# Shield.net
KiCad netlist of a schematic drawn in EAGLE
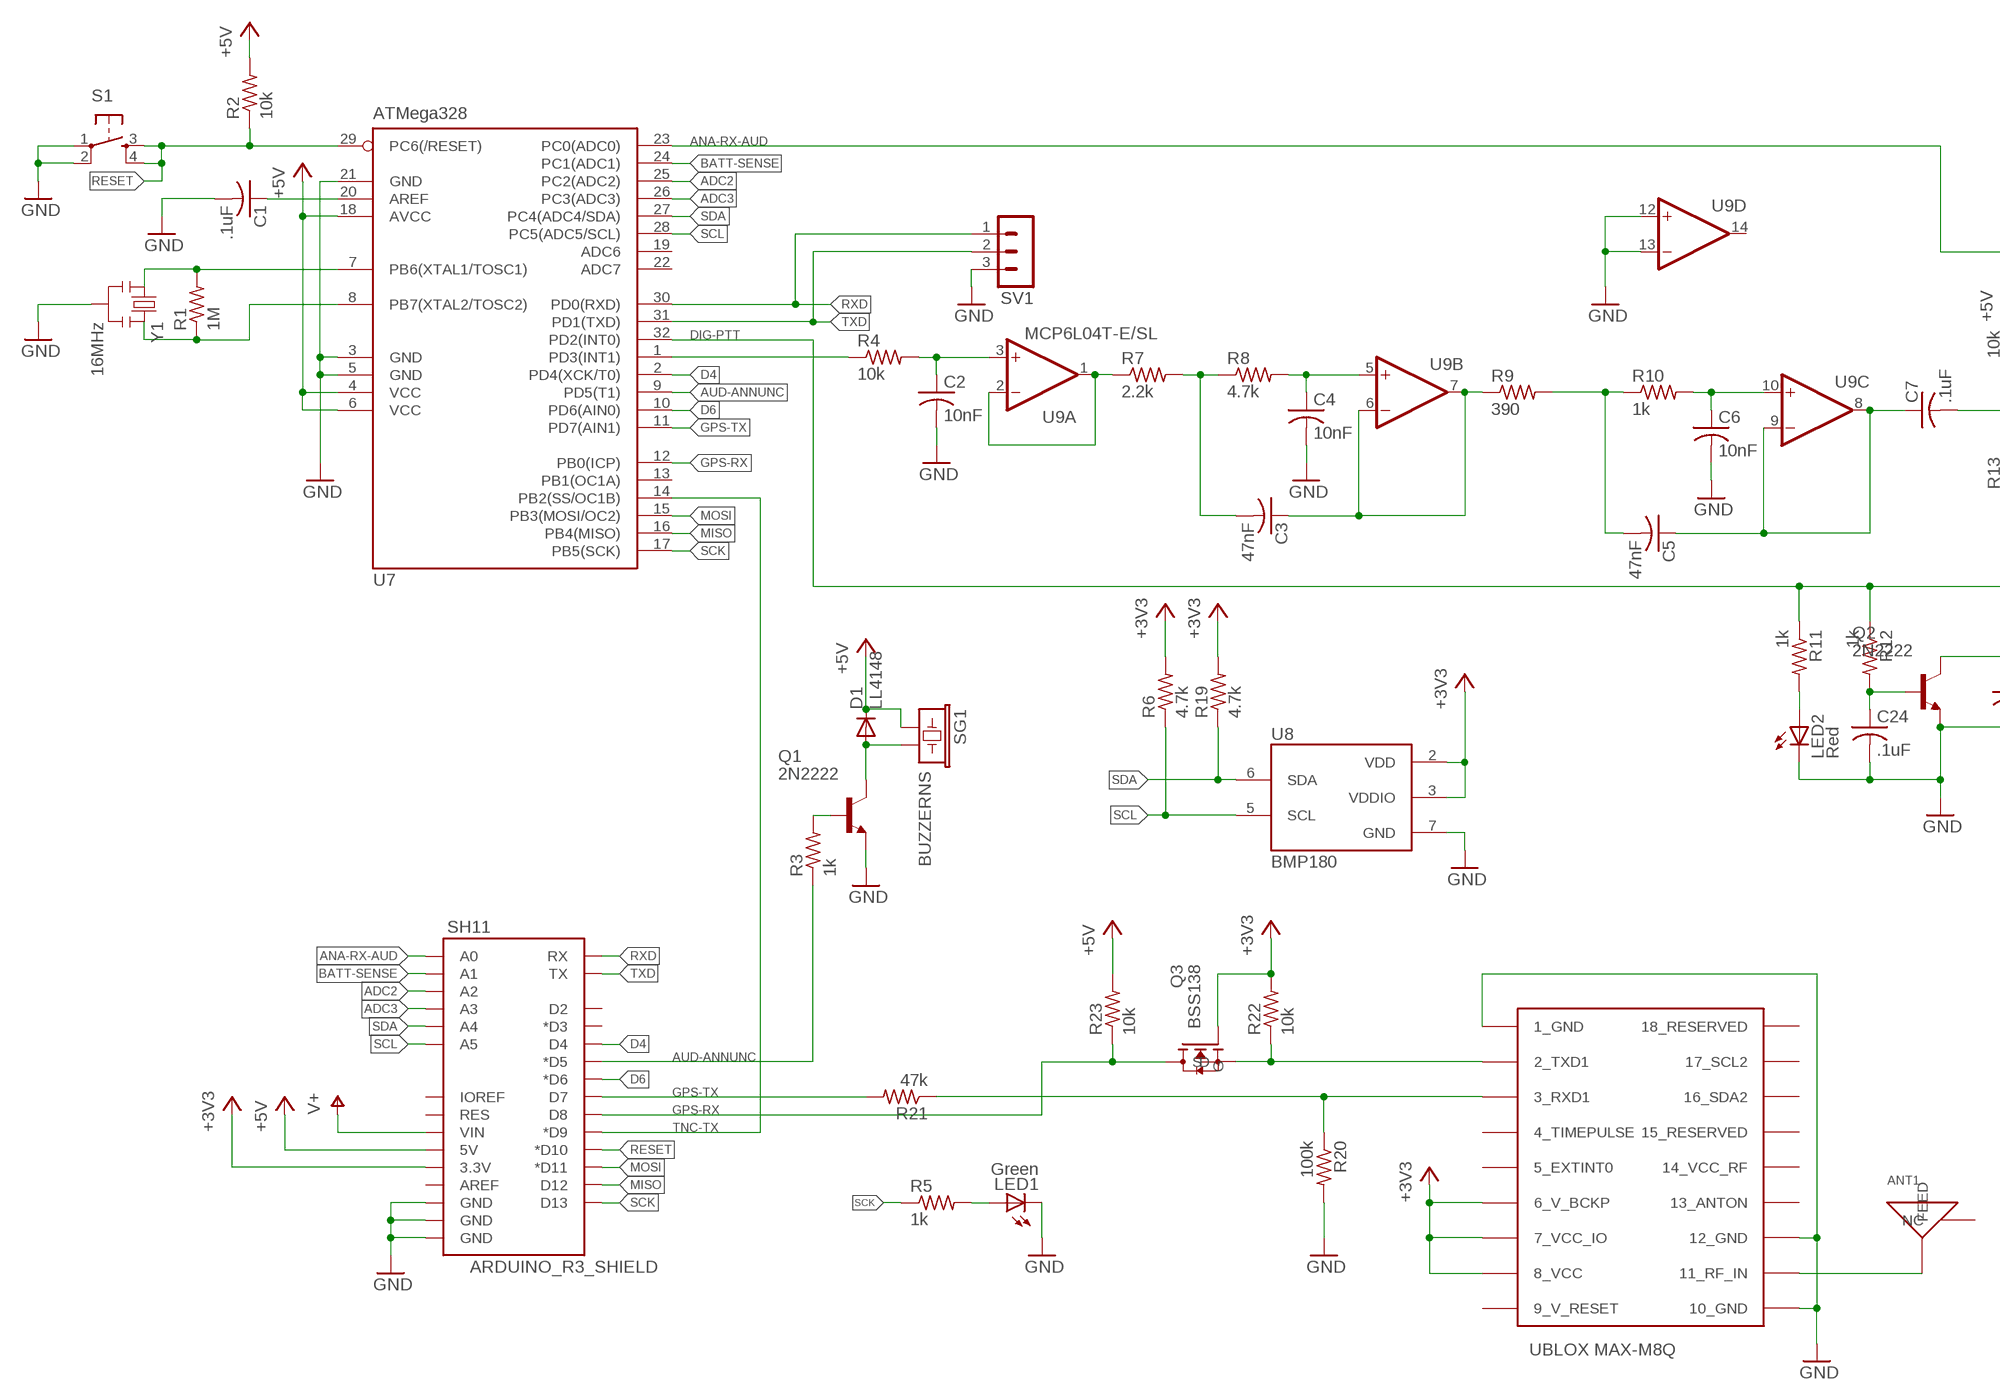
[diagram p0: schematic, sheet 1, part 1 of 2]
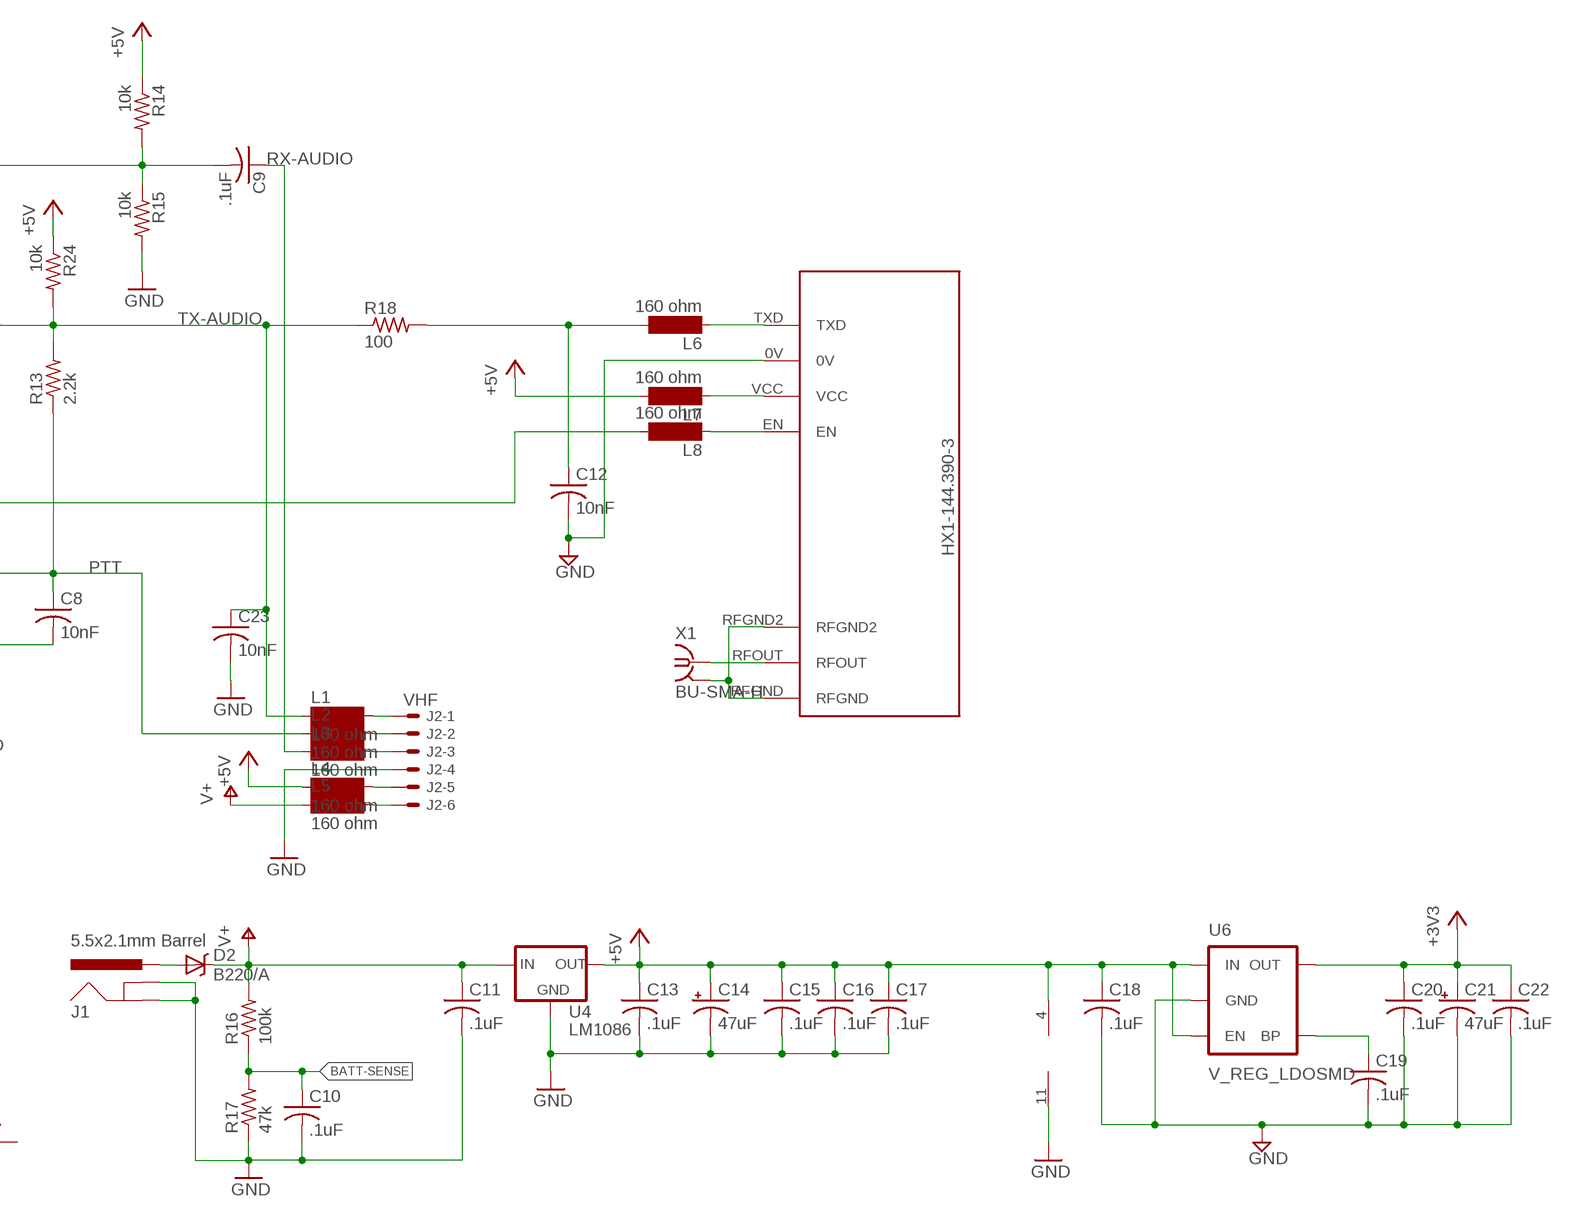
[diagram p1: schematic, sheet 1, part 2 of 2]

(export (version "E")
  (design (tool "Eeschema 10.0.6"))
  (components
    (comp (ref "ANT1")
      (value "GPS_ANT_SMDBAR")
      (footprint "eagle-import:1575AT43A40")
      (libsource (lib "eagle-import") (part "GPS_ANT_SMDBAR"))
    )
    (comp (ref "C1")
      (value ".1uF")
      (footprint "eagle-import:C0805")
      (libsource (lib "eagle-import") (part "C-USC0805"))
    )
    (comp (ref "C2")
      (value "10nF")
      (footprint "eagle-import:C0805")
      (libsource (lib "eagle-import") (part "C-USC0805"))
    )
    (comp (ref "C3")
      (value "47nF")
      (footprint "eagle-import:C0805")
      (libsource (lib "eagle-import") (part "C-USC0805"))
    )
    (comp (ref "C4")
      (value "10nF")
      (footprint "eagle-import:C0805")
      (libsource (lib "eagle-import") (part "C-USC0805"))
    )
    (comp (ref "C5")
      (value "47nF")
      (footprint "eagle-import:C0805")
      (libsource (lib "eagle-import") (part "C-USC0805"))
    )
    (comp (ref "C6")
      (value "10nF")
      (footprint "eagle-import:C0805")
      (libsource (lib "eagle-import") (part "C-USC0805"))
    )
    (comp (ref "C7")
      (value ".1uF")
      (footprint "eagle-import:C0805")
      (libsource (lib "eagle-import") (part "C-USC0805"))
    )
    (comp (ref "C8")
      (value "10nF")
      (footprint "eagle-import:C0805")
      (libsource (lib "eagle-import") (part "C-USC0805"))
    )
    (comp (ref "C9")
      (value ".1uF")
      (footprint "eagle-import:C0805")
      (libsource (lib "eagle-import") (part "C-USC0805"))
    )
    (comp (ref "C10")
      (value ".1uF")
      (footprint "eagle-import:C0805")
      (libsource (lib "eagle-import") (part "C-USC0805"))
    )
    (comp (ref "C11")
      (value ".1uF")
      (footprint "eagle-import:C0805")
      (libsource (lib "eagle-import") (part "C-USC0805"))
    )
    (comp (ref "C12")
      (value "10nF")
      (footprint "eagle-import:C0805")
      (libsource (lib "eagle-import") (part "C-USC0805"))
    )
    (comp (ref "C13")
      (value ".1uF")
      (footprint "eagle-import:C0805")
      (libsource (lib "eagle-import") (part "C-USC0805"))
    )
    (comp (ref "C14")
      (value "47uF")
      (footprint "eagle-import:153CLV-0605")
      (libsource (lib "eagle-import") (part "CPOL-US153CLV-0605"))
    )
    (comp (ref "C15")
      (value ".1uF")
      (footprint "eagle-import:C0805")
      (libsource (lib "eagle-import") (part "C-USC0805"))
    )
    (comp (ref "C16")
      (value ".1uF")
      (footprint "eagle-import:C0805")
      (libsource (lib "eagle-import") (part "C-USC0805"))
    )
    (comp (ref "C17")
      (value ".1uF")
      (footprint "eagle-import:C0805")
      (libsource (lib "eagle-import") (part "C-USC0805"))
    )
    (comp (ref "C18")
      (value ".1uF")
      (footprint "eagle-import:C0805")
      (libsource (lib "eagle-import") (part "C-USC0805"))
    )
    (comp (ref "C19")
      (value ".1uF")
      (footprint "eagle-import:C0805")
      (libsource (lib "eagle-import") (part "C-USC0805"))
    )
    (comp (ref "C20")
      (value ".1uF")
      (footprint "eagle-import:C0805")
      (libsource (lib "eagle-import") (part "C-USC0805"))
    )
    (comp (ref "C21")
      (value "47uF")
      (footprint "eagle-import:153CLV-0605")
      (libsource (lib "eagle-import") (part "CPOL-US153CLV-0605"))
    )
    (comp (ref "C22")
      (value ".1uF")
      (footprint "eagle-import:C0805")
      (libsource (lib "eagle-import") (part "C-USC0805"))
    )
    (comp (ref "C23")
      (value "10nF")
      (footprint "eagle-import:C0805")
      (libsource (lib "eagle-import") (part "C-USC0805"))
    )
    (comp (ref "C24")
      (value ".1uF")
      (footprint "eagle-import:C0805")
      (libsource (lib "eagle-import") (part "C-USC0805"))
    )
    (comp (ref "D1")
      (value "LL4148")
      (footprint "eagle-import:MINIMELF")
      (libsource (lib "eagle-import") (part "DIODE-MINIMELF"))
    )
    (comp (ref "D2")
      (value "B220/A")
      (footprint "eagle-import:SMA-DIODE")
      (libsource (lib "eagle-import") (part "B340A"))
    )
    (comp (ref "J1")
      (value "5.5x2.1mm Barrel")
      (footprint "eagle-import:POWER_JACK_SMD")
      (libsource (lib "eagle-import") (part "POWER_JACKSMD"))
    )
    (comp (ref "J2")
      (value "VHF")
      (footprint "eagle-import:7395-06")
      (fields (field (name "DIGIKEY") "WM4304-ND"))
      (libsource (lib "eagle-import") (part "22-?-0605-7068"))
    )
    (comp (ref "L1")
      (value "160 ohm")
      (footprint "eagle-import:SM-1206")
      (libsource (lib "eagle-import") (part "SM-1206"))
    )
    (comp (ref "L2")
      (value "160 ohm")
      (footprint "eagle-import:SM-1206")
      (libsource (lib "eagle-import") (part "SM-1206"))
    )
    (comp (ref "L3")
      (value "160 ohm")
      (footprint "eagle-import:SM-1206")
      (libsource (lib "eagle-import") (part "SM-1206"))
    )
    (comp (ref "L4")
      (value "160 ohm")
      (footprint "eagle-import:SM-1206")
      (libsource (lib "eagle-import") (part "SM-1206"))
    )
    (comp (ref "L5")
      (value "160 ohm")
      (footprint "eagle-import:SM-1206")
      (libsource (lib "eagle-import") (part "SM-1206"))
    )
    (comp (ref "L6")
      (value "160 ohm")
      (footprint "eagle-import:SM-1206")
      (libsource (lib "eagle-import") (part "SM-1206"))
    )
    (comp (ref "L7")
      (value "160 ohm")
      (footprint "eagle-import:SM-1206")
      (libsource (lib "eagle-import") (part "SM-1206"))
    )
    (comp (ref "L8")
      (value "160 ohm")
      (footprint "eagle-import:SM-1206")
      (libsource (lib "eagle-import") (part "SM-1206"))
    )
    (comp (ref "LED1")
      (value "Green")
      (footprint "eagle-import:CHIPLED_1206")
      (libsource (lib "eagle-import") (part "LEDCHIPLED_1206"))
    )
    (comp (ref "LED2")
      (value "Red")
      (footprint "eagle-import:CHIPLED_1206")
      (libsource (lib "eagle-import") (part "LEDCHIPLED_1206"))
    )
    (comp (ref "Q1")
      (value "2N2222")
      (footprint "eagle-import:SOT23-BEC")
      (libsource (lib "eagle-import") (part "BC817SMD-16LT1"))
    )
    (comp (ref "Q2")
      (value "2N2222")
      (footprint "eagle-import:SOT23-BEC")
      (libsource (lib "eagle-import") (part "BC817SMD-16LT1"))
    )
    (comp (ref "Q3")
      (value "BSS138")
      (footprint "eagle-import:BSS138")
      (libsource (lib "eagle-import") (part "BSS138"))
    )
    (comp (ref "R1")
      (value "1M")
      (footprint "eagle-import:R0805")
      (libsource (lib "eagle-import") (part "R-US_R0805"))
    )
    (comp (ref "R2")
      (value "10k")
      (footprint "eagle-import:R0805")
      (libsource (lib "eagle-import") (part "R-US_R0805"))
    )
    (comp (ref "R3")
      (value "1k")
      (footprint "eagle-import:R0805")
      (libsource (lib "eagle-import") (part "R-US_R0805"))
    )
    (comp (ref "R4")
      (value "10k")
      (footprint "eagle-import:R0805")
      (libsource (lib "eagle-import") (part "R-US_R0805"))
    )
    (comp (ref "R5")
      (value "1k")
      (footprint "eagle-import:R0805")
      (libsource (lib "eagle-import") (part "R-US_R0805"))
    )
    (comp (ref "R6")
      (value "4.7k")
      (footprint "eagle-import:R0805")
      (libsource (lib "eagle-import") (part "R-US_R0805"))
    )
    (comp (ref "R7")
      (value "2.2k")
      (footprint "eagle-import:R0805")
      (libsource (lib "eagle-import") (part "R-US_R0805"))
    )
    (comp (ref "R8")
      (value "4.7k")
      (footprint "eagle-import:R0805")
      (libsource (lib "eagle-import") (part "R-US_R0805"))
    )
    (comp (ref "R9")
      (value "390")
      (footprint "eagle-import:R0805")
      (libsource (lib "eagle-import") (part "R-US_R0805"))
    )
    (comp (ref "R10")
      (value "1k")
      (footprint "eagle-import:R0805")
      (libsource (lib "eagle-import") (part "R-US_R0805"))
    )
    (comp (ref "R11")
      (value "1k")
      (footprint "eagle-import:R0805")
      (libsource (lib "eagle-import") (part "R-US_R0805"))
    )
    (comp (ref "R12")
      (value "1k")
      (footprint "eagle-import:R0805")
      (libsource (lib "eagle-import") (part "R-US_R0805"))
    )
    (comp (ref "R13")
      (value "2.2k")
      (footprint "eagle-import:R0805")
      (libsource (lib "eagle-import") (part "R-US_R0805"))
    )
    (comp (ref "R14")
      (value "10k")
      (footprint "eagle-import:R0805")
      (libsource (lib "eagle-import") (part "R-US_R0805"))
    )
    (comp (ref "R15")
      (value "10k")
      (footprint "eagle-import:R0805")
      (libsource (lib "eagle-import") (part "R-US_R0805"))
    )
    (comp (ref "R16")
      (value "100k")
      (footprint "eagle-import:R0805")
      (libsource (lib "eagle-import") (part "R-US_R0805"))
    )
    (comp (ref "R17")
      (value "47k")
      (footprint "eagle-import:R0805")
      (libsource (lib "eagle-import") (part "R-US_R0805"))
    )
    (comp (ref "R18")
      (value "100")
      (footprint "eagle-import:R0805")
      (libsource (lib "eagle-import") (part "R-US_R0805"))
    )
    (comp (ref "R19")
      (value "4.7k")
      (footprint "eagle-import:R0805")
      (libsource (lib "eagle-import") (part "R-US_R0805"))
    )
    (comp (ref "R20")
      (value "100k")
      (footprint "eagle-import:R0805")
      (libsource (lib "eagle-import") (part "R-US_R0805"))
    )
    (comp (ref "R21")
      (value "47k")
      (footprint "eagle-import:R0805")
      (libsource (lib "eagle-import") (part "R-US_R0805"))
    )
    (comp (ref "R22")
      (value "10k")
      (footprint "eagle-import:R0805")
      (libsource (lib "eagle-import") (part "R-US_R0805"))
    )
    (comp (ref "R23")
      (value "10k")
      (footprint "eagle-import:R0805")
      (libsource (lib "eagle-import") (part "R-US_R0805"))
    )
    (comp (ref "R24")
      (value "10k")
      (footprint "eagle-import:R0805")
      (libsource (lib "eagle-import") (part "R-US_R0805"))
    )
    (comp (ref "S1")
      (value "TAC_SWITCHSMD")
      (footprint "eagle-import:TACTILE_SWITCH_SMD")
      (libsource (lib "eagle-import") (part "TAC_SWITCHSMD"))
    )
    (comp (ref "SG1")
      (value "BUZZERNS")
      (footprint "eagle-import:BUZZER-12MM-NS")
      (libsource (lib "eagle-import") (part "BUZZERNS"))
    )
    (comp (ref "SH11")
      (value "ARDUINO_R3_SHIELD")
      (footprint "eagle-import:UNO_R3_SHIELD")
      (libsource (lib "eagle-import") (part "ARDUINO_R3_SHIELD"))
    )
    (comp (ref "SV1")
      (value "MA03-1")
      (footprint "eagle-import:MA03-1")
      (libsource (lib "eagle-import") (part "MA03-1"))
    )
    (comp (ref "U3")
      (value "UBLOX_MAX")
      (footprint "eagle-import:UBLOX_MAX")
      (fields (field (name "ALT-PART") "UBLOX MAX-M8Q"))
      (libsource (lib "eagle-import") (part "UBLOX_MAX"))
    )
    (comp (ref "U4")
      (value "LM1086")
      (footprint "eagle-import:TO263")
      (libsource (lib "eagle-import") (part "LM1086TO263"))
    )
    (comp (ref "U5")
      (value "RADIOMETRIX-HX1")
      (footprint "eagle-import:RADIOMETRIX-HX1")
      (fields (field (name "ALT-PART") "HX1-144.390-3"))
      (libsource (lib "eagle-import") (part "RADIOMETRIX-HX1"))
    )
    (comp (ref "U6")
      (value "V_REG_LDOSMD")
      (footprint "eagle-import:SOT23-5")
      (libsource (lib "eagle-import") (part "V_REG_LDOSMD"))
    )
    (comp (ref "U7")
      (value "ATMega328")
      (footprint "eagle-import:TQFP32-08")
      (fields (field (name "MPN") "ATMEGA8-16AU"))
      (libsource (lib "eagle-import") (part "MEGA8-AI"))
    )
    (comp (ref "U8")
      (value "BMP180")
      (footprint "eagle-import:BMP180")
      (libsource (lib "eagle-import") (part "BMP180"))
    )
    (comp (ref "U9")
      (value "LMV324M")
      (footprint "eagle-import:SO14")
      (fields (field (name "ALT-PART") "MCP6L04T-E/SL") (field (name "DIGIKEY") "MCP6L04T-E/SLCT-ND"))
      (libsource (lib "eagle-import") (part "LMV324?M"))
    )
    (comp (ref "X1")
      (value "BU-SMA-H")
      (footprint "eagle-import:BU-SMA-H")
      (libsource (lib "eagle-import") (part "BU-SMA-H"))
    )
    (comp (ref "Y1")
      (value "16MHz")
      (footprint "eagle-import:RESONATOR-SMD")
      (libsource (lib "eagle-import") (part "RESONATOR16MHZ"))
    )
  )
  (nets
    (net (code "1") (name "+3V3") (class "Default")
      (node (ref "C20") (pin "1") (pinfunction "1_1") (pintype "passive"))
      (node (ref "C21") (pin "+") (pinfunction "+_+") (pintype "passive"))
      (node (ref "C22") (pin "1") (pinfunction "1_1") (pintype "passive"))
      (node (ref "Q3") (pin "G") (pinfunction "G_G") (pintype "passive"))
      (node (ref "R19") (pin "2") (pinfunction "2_2") (pintype "passive"))
      (node (ref "R22") (pin "2") (pinfunction "2_2") (pintype "passive"))
      (node (ref "R6") (pin "2") (pinfunction "2_2") (pintype "passive"))
      (node (ref "SH11") (pin "3.3V") (pinfunction "3.3V_3.3V") (pintype "bidirectional"))
      (node (ref "U3") (pin "6_V_BCKP") (pinfunction "6_V_BCKP_6_V_BCKP") (pintype "bidirectional"))
      (node (ref "U3") (pin "7_VCC_IO") (pinfunction "7_VCC_IO_7_VCC_IO") (pintype "power_in"))
      (node (ref "U3") (pin "8_VCC") (pinfunction "8_VCC_8_VCC") (pintype "power_in"))
      (node (ref "U6") (pin "5") (pinfunction "OUT_5") (pintype "passive"))
      (node (ref "U8") (pin "2") (pinfunction "VDD_2") (pintype "power_in"))
      (node (ref "U8") (pin "3") (pinfunction "VDDIO_3") (pintype "power_in"))
    )
    (net (code "2") (name "+5V") (class "Default")
      (node (ref "C13") (pin "1") (pinfunction "1_1") (pintype "passive"))
      (node (ref "C14") (pin "+") (pinfunction "+_+") (pintype "passive"))
      (node (ref "C15") (pin "1") (pinfunction "1_1") (pintype "passive"))
      (node (ref "C16") (pin "1") (pinfunction "1_1") (pintype "passive"))
      (node (ref "C17") (pin "1") (pinfunction "1_1") (pintype "passive"))
      (node (ref "C18") (pin "1") (pinfunction "1_1") (pintype "passive"))
      (node (ref "D1") (pin "C") (pinfunction "C_C") (pintype "passive"))
      (node (ref "L4") (pin "1") (pinfunction "1_1") (pintype "passive"))
      (node (ref "L7") (pin "2") (pinfunction "2_2") (pintype "passive"))
      (node (ref "R14") (pin "1") (pinfunction "1_1") (pintype "passive"))
      (node (ref "R2") (pin "2") (pinfunction "2_2") (pintype "passive"))
      (node (ref "R23") (pin "2") (pinfunction "2_2") (pintype "passive"))
      (node (ref "R24") (pin "1") (pinfunction "1_1") (pintype "passive"))
      (node (ref "SG1") (pin "+") (pinfunction "1_+") (pintype "passive"))
      (node (ref "SH11") (pin "5V") (pinfunction "5V_5V") (pintype "bidirectional"))
      (node (ref "U4") (pin "2") (pinfunction "OUT_2") (pintype "passive"))
      (node (ref "U6") (pin "1") (pinfunction "IN_1") (pintype "input"))
      (node (ref "U6") (pin "3") (pinfunction "EN_3") (pintype "input"))
      (node (ref "U7") (pin "18") (pinfunction "AVCC_18") (pintype "power_in"))
      (node (ref "U7") (pin "4") (pinfunction "VCC_4") (pintype "power_in"))
      (node (ref "U7") (pin "6") (pinfunction "VCC_6") (pintype "power_in"))
      (node (ref "U9") (pin "4") (pinfunction "V+_4") (pintype "power_in"))
    )
    (net (code "3") (name "/9_V_RESET") (class "Default")
      (node (ref "U3") (pin "9_V_RESET") (pinfunction "9_V_RESET_9_V_RESET") (pintype "power_in"))
    )
    (net (code "4") (name "/DIG-PTT") (class "Default")
      (node (ref "L8") (pin "2") (pinfunction "2_2") (pintype "passive"))
      (node (ref "R11") (pin "1") (pinfunction "1_1") (pintype "passive"))
      (node (ref "R12") (pin "1") (pinfunction "1_1") (pintype "passive"))
      (node (ref "U7") (pin "32") (pinfunction "PD2(INT0)_32") (pintype "bidirectional"))
    )
    (net (code "5") (name "/PTT") (class "Default")
      (node (ref "C8") (pin "1") (pinfunction "1_1") (pintype "passive"))
      (node (ref "L2") (pin "1") (pinfunction "1_1") (pintype "passive"))
      (node (ref "Q2") (pin "C") (pinfunction "C_C") (pintype "passive"))
      (node (ref "R13") (pin "1") (pinfunction "1_1") (pintype "passive"))
    )
    (net (code "6") (name "/RX-AUDIO") (class "Default")
      (node (ref "C9") (pin "1") (pinfunction "1_1") (pintype "passive"))
      (node (ref "L3") (pin "1") (pinfunction "1_1") (pintype "passive"))
    )
    (net (code "7") (name "/TNC-TX") (class "Default")
      (node (ref "SH11") (pin "D9") (pinfunction "*D9_D9") (pintype "bidirectional"))
      (node (ref "U7") (pin "14") (pinfunction "PB2(SS/OC1B)_14") (pintype "bidirectional"))
    )
    (net (code "8") (name "/TX-AUDIO") (class "Default")
      (node (ref "C23") (pin "1") (pinfunction "1_1") (pintype "passive"))
      (node (ref "C7") (pin "2") (pinfunction "2_2") (pintype "passive"))
      (node (ref "L1") (pin "1") (pinfunction "1_1") (pintype "passive"))
      (node (ref "R13") (pin "2") (pinfunction "2_2") (pintype "passive"))
      (node (ref "R18") (pin "1") (pinfunction "1_1") (pintype "passive"))
      (node (ref "R24") (pin "2") (pinfunction "2_2") (pintype "passive"))
    )
    (net (code "9") (name "ADC2") (class "Default")
      (node (ref "SH11") (pin "A2") (pinfunction "A2_A2") (pintype "bidirectional"))
      (node (ref "U7") (pin "25") (pinfunction "PC2(ADC2)_25") (pintype "bidirectional"))
    )
    (net (code "10") (name "ADC3") (class "Default")
      (node (ref "SH11") (pin "A3") (pinfunction "A3_A3") (pintype "bidirectional"))
      (node (ref "U7") (pin "26") (pinfunction "PC3(ADC3)_26") (pintype "bidirectional"))
    )
    (net (code "11") (name "ANA-RX-AUD") (class "Default")
      (node (ref "C9") (pin "2") (pinfunction "2_2") (pintype "passive"))
      (node (ref "R14") (pin "2") (pinfunction "2_2") (pintype "passive"))
      (node (ref "R15") (pin "1") (pinfunction "1_1") (pintype "passive"))
      (node (ref "SH11") (pin "A0") (pinfunction "A0_A0") (pintype "bidirectional"))
      (node (ref "U7") (pin "23") (pinfunction "PC0(ADC0)_23") (pintype "bidirectional"))
    )
    (net (code "12") (name "AUD-ANNUNC") (class "Default")
      (node (ref "R3") (pin "1") (pinfunction "1_1") (pintype "passive"))
      (node (ref "SH11") (pin "D5") (pinfunction "*D5_D5") (pintype "bidirectional"))
      (node (ref "U7") (pin "9") (pinfunction "PD5(T1)_9") (pintype "bidirectional"))
    )
    (net (code "13") (name "BATT-SENSE") (class "Default")
      (node (ref "C10") (pin "1") (pinfunction "1_1") (pintype "passive"))
      (node (ref "R16") (pin "1") (pinfunction "1_1") (pintype "passive"))
      (node (ref "R17") (pin "2") (pinfunction "2_2") (pintype "passive"))
      (node (ref "SH11") (pin "A1") (pinfunction "A1_A1") (pintype "bidirectional"))
      (node (ref "U7") (pin "24") (pinfunction "PC1(ADC1)_24") (pintype "bidirectional"))
    )
    (net (code "14") (name "D4") (class "Default")
      (node (ref "SH11") (pin "D4") (pinfunction "D4_D4") (pintype "bidirectional"))
      (node (ref "U7") (pin "2") (pinfunction "PD4(XCK/T0)_2") (pintype "bidirectional"))
    )
    (net (code "15") (name "D6") (class "Default")
      (node (ref "SH11") (pin "D6") (pinfunction "*D6_D6") (pintype "bidirectional"))
      (node (ref "U7") (pin "10") (pinfunction "PD6(AIN0)_10") (pintype "bidirectional"))
    )
    (net (code "16") (name "GND") (class "Default")
      (node (ref "C1") (pin "2") (pinfunction "2_2") (pintype "passive"))
      (node (ref "C10") (pin "2") (pinfunction "2_2") (pintype "passive"))
      (node (ref "C11") (pin "2") (pinfunction "2_2") (pintype "passive"))
      (node (ref "C12") (pin "2") (pinfunction "2_2") (pintype "passive"))
      (node (ref "C13") (pin "2") (pinfunction "2_2") (pintype "passive"))
      (node (ref "C14") (pin "-") (pinfunction "-_-") (pintype "passive"))
      (node (ref "C15") (pin "2") (pinfunction "2_2") (pintype "passive"))
      (node (ref "C16") (pin "2") (pinfunction "2_2") (pintype "passive"))
      (node (ref "C17") (pin "2") (pinfunction "2_2") (pintype "passive"))
      (node (ref "C18") (pin "2") (pinfunction "2_2") (pintype "passive"))
      (node (ref "C19") (pin "2") (pinfunction "2_2") (pintype "passive"))
      (node (ref "C2") (pin "2") (pinfunction "2_2") (pintype "passive"))
      (node (ref "C20") (pin "2") (pinfunction "2_2") (pintype "passive"))
      (node (ref "C21") (pin "-") (pinfunction "-_-") (pintype "passive"))
      (node (ref "C22") (pin "2") (pinfunction "2_2") (pintype "passive"))
      (node (ref "C23") (pin "2") (pinfunction "2_2") (pintype "passive"))
      (node (ref "C24") (pin "2") (pinfunction "2_2") (pintype "passive"))
      (node (ref "C4") (pin "2") (pinfunction "2_2") (pintype "passive"))
      (node (ref "C6") (pin "2") (pinfunction "2_2") (pintype "passive"))
      (node (ref "C8") (pin "2") (pinfunction "2_2") (pintype "passive"))
      (node (ref "J1") (pin "GND") (pinfunction "GNDBREAK_GND") (pintype "bidirectional"))
      (node (ref "J1") (pin "P$4") (pinfunction "GND_P$4") (pintype "bidirectional"))
      (node (ref "J2") (pin "4") (pinfunction "S_4") (pintype "passive"))
      (node (ref "LED1") (pin "C") (pinfunction "C_C") (pintype "passive"))
      (node (ref "LED2") (pin "C") (pinfunction "C_C") (pintype "passive"))
      (node (ref "Q1") (pin "E") (pinfunction "E_E") (pintype "passive"))
      (node (ref "Q2") (pin "E") (pinfunction "E_E") (pintype "passive"))
      (node (ref "R15") (pin "2") (pinfunction "2_2") (pintype "passive"))
      (node (ref "R17") (pin "1") (pinfunction "1_1") (pintype "passive"))
      (node (ref "R20") (pin "2") (pinfunction "2_2") (pintype "passive"))
      (node (ref "S1") (pin "1") (pinfunction "1_1") (pintype "passive"))
      (node (ref "S1") (pin "2") (pinfunction "2_2") (pintype "passive"))
      (node (ref "SH11") (pin "GND@0") (pinfunction "GND_GND@0") (pintype "bidirectional"))
      (node (ref "SH11") (pin "GND@1") (pinfunction "GND_GND@1") (pintype "bidirectional"))
      (node (ref "SH11") (pin "GND@2") (pinfunction "GND_GND@2") (pintype "bidirectional"))
      (node (ref "SV1") (pin "3") (pinfunction "3_3") (pintype "passive"))
      (node (ref "U3") (pin "10_GND") (pinfunction "10_GND_10_GND") (pintype "power_in"))
      (node (ref "U3") (pin "12_GND") (pinfunction "12_GND_12_GND") (pintype "power_in"))
      (node (ref "U3") (pin "1_GND") (pinfunction "1_GND_1_GND") (pintype "power_in"))
      (node (ref "U4") (pin "1") (pinfunction "GND_1") (pintype "input"))
      (node (ref "U5") (pin "0V") (pinfunction "0V_0V") (pintype "bidirectional"))
      (node (ref "U6") (pin "2") (pinfunction "GND_2") (pintype "input"))
      (node (ref "U7") (pin "21") (pinfunction "GND_21") (pintype "power_in"))
      (node (ref "U7") (pin "3") (pinfunction "GND_3") (pintype "power_in"))
      (node (ref "U7") (pin "5") (pinfunction "GND_5") (pintype "power_in"))
      (node (ref "U8") (pin "7") (pinfunction "GND_7") (pintype "power_in"))
      (node (ref "U9") (pin "11") (pinfunction "V-_11") (pintype "power_in"))
      (node (ref "U9") (pin "12") (pinfunction "+IN_12") (pintype "input"))
      (node (ref "U9") (pin "13") (pinfunction "-IN_13") (pintype "input"))
      (node (ref "Y1") (pin "2") (pinfunction "2_2") (pintype "passive"))
    )
    (net (code "17") (name "GPS-RX") (class "Default")
      (node (ref "Q3") (pin "D") (pinfunction "D_D") (pintype "passive"))
      (node (ref "R23") (pin "1") (pinfunction "1_1") (pintype "passive"))
      (node (ref "SH11") (pin "D8") (pinfunction "D8_D8") (pintype "bidirectional"))
      (node (ref "U7") (pin "12") (pinfunction "PB0(ICP)_12") (pintype "bidirectional"))
    )
    (net (code "18") (name "GPS-TX") (class "Default")
      (node (ref "R21") (pin "2") (pinfunction "2_2") (pintype "passive"))
      (node (ref "SH11") (pin "D7") (pinfunction "D7_D7") (pintype "bidirectional"))
      (node (ref "U7") (pin "11") (pinfunction "PD7(AIN1)_11") (pintype "bidirectional"))
    )
    (net (code "19") (name "MISO") (class "Default")
      (node (ref "SH11") (pin "D12") (pinfunction "D12_D12") (pintype "bidirectional"))
      (node (ref "U7") (pin "16") (pinfunction "PB4(MISO)_16") (pintype "bidirectional"))
    )
    (net (code "20") (name "MOSI") (class "Default")
      (node (ref "SH11") (pin "D11") (pinfunction "*D11_D11") (pintype "bidirectional"))
      (node (ref "U7") (pin "15") (pinfunction "PB3(MOSI/OC2)_15") (pintype "bidirectional"))
    )
    (net (code "21") (name "Net-(ANT1-PadFEED)") (class "Default")
      (node (ref "ANT1") (pin "FEED") (pinfunction "FEED_FEED") (pintype "bidirectional"))
      (node (ref "U3") (pin "11_RF_IN") (pinfunction "11_RF_IN_11_RF_IN") (pintype "bidirectional"))
    )
    (net (code "22") (name "Net-(C3-Pad2)") (class "Default")
      (node (ref "C3") (pin "2") (pinfunction "2_2") (pintype "passive"))
      (node (ref "R7") (pin "2") (pinfunction "2_2") (pintype "passive"))
      (node (ref "R8") (pin "1") (pinfunction "1_1") (pintype "passive"))
    )
    (net (code "23") (name "Net-(C5-Pad2)") (class "Default")
      (node (ref "C5") (pin "2") (pinfunction "2_2") (pintype "passive"))
      (node (ref "R10") (pin "1") (pinfunction "1_1") (pintype "passive"))
      (node (ref "R9") (pin "2") (pinfunction "2_2") (pintype "passive"))
    )
    (net (code "24") (name "Net-(C12-Pad1)") (class "Default")
      (node (ref "C12") (pin "1") (pinfunction "1_1") (pintype "passive"))
      (node (ref "L6") (pin "2") (pinfunction "2_2") (pintype "passive"))
      (node (ref "R18") (pin "2") (pinfunction "2_2") (pintype "passive"))
    )
    (net (code "25") (name "Net-(C24-Pad1)") (class "Default")
      (node (ref "C24") (pin "1") (pinfunction "1_1") (pintype "passive"))
      (node (ref "Q2") (pin "B") (pinfunction "B_B") (pintype "passive"))
      (node (ref "R12") (pin "2") (pinfunction "2_2") (pintype "passive"))
    )
    (net (code "26") (name "Net-(J1-PWR)") (class "Default")
      (node (ref "D2") (pin "A") (pinfunction "A_A") (pintype "passive"))
      (node (ref "J1") (pin "VIN0") (pinfunction "PWR_VIN0") (pintype "bidirectional"))
    )
    (net (code "27") (name "Net-(J2A-S)") (class "Default")
      (node (ref "J2") (pin "1") (pinfunction "S_1") (pintype "passive"))
      (node (ref "L1") (pin "2") (pinfunction "2_2") (pintype "passive"))
    )
    (net (code "28") (name "Net-(J2B-S)") (class "Default")
      (node (ref "J2") (pin "2") (pinfunction "S_2") (pintype "passive"))
      (node (ref "L2") (pin "2") (pinfunction "2_2") (pintype "passive"))
    )
    (net (code "29") (name "Net-(J2C-S)") (class "Default")
      (node (ref "J2") (pin "3") (pinfunction "S_3") (pintype "passive"))
      (node (ref "L3") (pin "2") (pinfunction "2_2") (pintype "passive"))
    )
    (net (code "30") (name "Net-(J2E-S)") (class "Default")
      (node (ref "J2") (pin "5") (pinfunction "S_5") (pintype "passive"))
      (node (ref "L4") (pin "2") (pinfunction "2_2") (pintype "passive"))
    )
    (net (code "31") (name "Net-(J2F-S)") (class "Default")
      (node (ref "J2") (pin "6") (pinfunction "S_6") (pintype "passive"))
      (node (ref "L5") (pin "2") (pinfunction "2_2") (pintype "passive"))
    )
    (net (code "32") (name "Net-(L6-Pad1)") (class "Default")
      (node (ref "L6") (pin "1") (pinfunction "1_1") (pintype "passive"))
      (node (ref "U5") (pin "TXD") (pinfunction "TXD_TXD") (pintype "bidirectional"))
    )
    (net (code "33") (name "Net-(L7-Pad1)") (class "Default")
      (node (ref "L7") (pin "1") (pinfunction "1_1") (pintype "passive"))
      (node (ref "U5") (pin "VCC") (pinfunction "VCC_VCC") (pintype "bidirectional"))
    )
    (net (code "34") (name "Net-(L8-Pad1)") (class "Default")
      (node (ref "L8") (pin "1") (pinfunction "1_1") (pintype "passive"))
      (node (ref "U5") (pin "EN") (pinfunction "EN_EN") (pintype "bidirectional"))
    )
    (net (code "35") (name "Net-(LED1-PadA)") (class "Default")
      (node (ref "LED1") (pin "A") (pinfunction "A_A") (pintype "passive"))
      (node (ref "R5") (pin "2") (pinfunction "2_2") (pintype "passive"))
    )
    (net (code "36") (name "Net-(LED2-PadA)") (class "Default")
      (node (ref "LED2") (pin "A") (pinfunction "A_A") (pintype "passive"))
      (node (ref "R11") (pin "2") (pinfunction "2_2") (pintype "passive"))
    )
    (net (code "37") (name "Net-(Q1-PadB)") (class "Default")
      (node (ref "Q1") (pin "B") (pinfunction "B_B") (pintype "passive"))
      (node (ref "R3") (pin "2") (pinfunction "2_2") (pintype "passive"))
    )
    (net (code "38") (name "Net-(Q3-PadS)") (class "Default")
      (node (ref "Q3") (pin "S") (pinfunction "S_S") (pintype "passive"))
      (node (ref "R22") (pin "1") (pinfunction "1_1") (pintype "passive"))
      (node (ref "U3") (pin "2_TXD1") (pinfunction "2_TXD1_2_TXD1") (pintype "bidirectional"))
    )
    (net (code "39") (name "Net-(R20-Pad1)") (class "Default")
      (node (ref "R20") (pin "1") (pinfunction "1_1") (pintype "passive"))
      (node (ref "R21") (pin "1") (pinfunction "1_1") (pintype "passive"))
      (node (ref "U3") (pin "3_RXD1") (pinfunction "3_RXD1_3_RXD1") (pintype "bidirectional"))
    )
    (net (code "40") (name "Net-(SG1-2)") (class "Default")
      (node (ref "D1") (pin "A") (pinfunction "A_A") (pintype "passive"))
      (node (ref "Q1") (pin "C") (pinfunction "C_C") (pintype "passive"))
      (node (ref "SG1") (pin "-") (pinfunction "2_-") (pintype "passive"))
    )
    (net (code "41") (name "Net-(U5-PadRFGND)") (class "Default")
      (node (ref "U5") (pin "RFGND") (pinfunction "RFGND_RFGND") (pintype "bidirectional"))
      (node (ref "U5") (pin "RFGND2") (pinfunction "RFGND2_RFGND2") (pintype "bidirectional"))
      (node (ref "X1") (pin "2") (pinfunction "2_2") (pintype "passive"))
      (node (ref "X1") (pin "3") (pinfunction "2_3") (pintype "passive"))
      (node (ref "X1") (pin "4") (pinfunction "2_4") (pintype "passive"))
      (node (ref "X1") (pin "5") (pinfunction "2_5") (pintype "passive"))
    )
    (net (code "42") (name "Net-(U5-PadRFOUT)") (class "Default")
      (node (ref "U5") (pin "RFOUT") (pinfunction "RFOUT_RFOUT") (pintype "bidirectional"))
      (node (ref "X1") (pin "1") (pinfunction "1_1") (pintype "passive"))
    )
    (net (code "43") (name "Net-(U6-BP)") (class "Default")
      (node (ref "C19") (pin "1") (pinfunction "1_1") (pintype "passive"))
      (node (ref "U6") (pin "4") (pinfunction "BP_4") (pintype "input"))
    )
    (net (code "44") (name "Net-(U7-AREF)") (class "Default")
      (node (ref "C1") (pin "1") (pinfunction "1_1") (pintype "passive"))
      (node (ref "U7") (pin "20") (pinfunction "AREF_20") (pintype "passive"))
    )
    (net (code "45") (name "Net-(U7-PB6(XTAL1{slash}TOSC1))") (class "Default")
      (node (ref "R1") (pin "2") (pinfunction "2_2") (pintype "passive"))
      (node (ref "U7") (pin "7") (pinfunction "PB6(XTAL1/TOSC1)_7") (pintype "bidirectional"))
      (node (ref "Y1") (pin "1") (pinfunction "1_1") (pintype "passive"))
    )
    (net (code "46") (name "Net-(U7-PB7(XTAL2{slash}TOSC2))") (class "Default")
      (node (ref "R1") (pin "1") (pinfunction "1_1") (pintype "passive"))
      (node (ref "U7") (pin "8") (pinfunction "PB7(XTAL2/TOSC2)_8") (pintype "bidirectional"))
      (node (ref "Y1") (pin "3") (pinfunction "3_3") (pintype "passive"))
    )
    (net (code "47") (name "Net-(U7-PD3(INT1))") (class "Default")
      (node (ref "R4") (pin "1") (pinfunction "1_1") (pintype "passive"))
      (node (ref "U7") (pin "1") (pinfunction "PD3(INT1)_1") (pintype "bidirectional"))
    )
    (net (code "48") (name "Net-(U9A-+IN)") (class "Default")
      (node (ref "C2") (pin "1") (pinfunction "1_1") (pintype "passive"))
      (node (ref "R4") (pin "2") (pinfunction "2_2") (pintype "passive"))
      (node (ref "U9") (pin "3") (pinfunction "+IN_3") (pintype "input"))
    )
    (net (code "49") (name "Net-(U9A--IN)") (class "Default")
      (node (ref "R7") (pin "1") (pinfunction "1_1") (pintype "passive"))
      (node (ref "U9") (pin "1") (pinfunction "OUT_1") (pintype "output"))
      (node (ref "U9") (pin "2") (pinfunction "-IN_2") (pintype "input"))
    )
    (net (code "50") (name "Net-(U9B-+IN)") (class "Default")
      (node (ref "C4") (pin "1") (pinfunction "1_1") (pintype "passive"))
      (node (ref "R8") (pin "2") (pinfunction "2_2") (pintype "passive"))
      (node (ref "U9") (pin "5") (pinfunction "+IN_5") (pintype "input"))
    )
    (net (code "51") (name "Net-(U9B--IN)") (class "Default")
      (node (ref "C3") (pin "1") (pinfunction "1_1") (pintype "passive"))
      (node (ref "R9") (pin "1") (pinfunction "1_1") (pintype "passive"))
      (node (ref "U9") (pin "6") (pinfunction "-IN_6") (pintype "input"))
      (node (ref "U9") (pin "7") (pinfunction "OUT_7") (pintype "output"))
    )
    (net (code "52") (name "Net-(U9C-+IN)") (class "Default")
      (node (ref "C6") (pin "1") (pinfunction "1_1") (pintype "passive"))
      (node (ref "R10") (pin "2") (pinfunction "2_2") (pintype "passive"))
      (node (ref "U9") (pin "10") (pinfunction "+IN_10") (pintype "input"))
    )
    (net (code "53") (name "Net-(U9C--IN)") (class "Default")
      (node (ref "C5") (pin "1") (pinfunction "1_1") (pintype "passive"))
      (node (ref "C7") (pin "1") (pinfunction "1_1") (pintype "passive"))
      (node (ref "U9") (pin "8") (pinfunction "OUT_8") (pintype "output"))
      (node (ref "U9") (pin "9") (pinfunction "-IN_9") (pintype "input"))
    )
    (net (code "54") (name "RESET") (class "Default")
      (node (ref "R2") (pin "1") (pinfunction "1_1") (pintype "passive"))
      (node (ref "S1") (pin "3") (pinfunction "3_3") (pintype "passive"))
      (node (ref "S1") (pin "4") (pinfunction "4_4") (pintype "passive"))
      (node (ref "SH11") (pin "D10") (pinfunction "*D10_D10") (pintype "bidirectional"))
      (node (ref "U7") (pin "29") (pinfunction "PC6(/RESET)_29") (pintype "bidirectional"))
    )
    (net (code "55") (name "RXD") (class "Default")
      (node (ref "SH11") (pin "RX") (pinfunction "RX_RX") (pintype "bidirectional"))
      (node (ref "SV1") (pin "1") (pinfunction "1_1") (pintype "passive"))
      (node (ref "U7") (pin "30") (pinfunction "PD0(RXD)_30") (pintype "bidirectional"))
    )
    (net (code "56") (name "SCK") (class "Default")
      (node (ref "R5") (pin "1") (pinfunction "1_1") (pintype "passive"))
      (node (ref "SH11") (pin "D13") (pinfunction "D13_D13") (pintype "bidirectional"))
      (node (ref "U7") (pin "17") (pinfunction "PB5(SCK)_17") (pintype "bidirectional"))
    )
    (net (code "57") (name "SCL") (class "Default")
      (node (ref "R6") (pin "1") (pinfunction "1_1") (pintype "passive"))
      (node (ref "SH11") (pin "A5") (pinfunction "A5_A5") (pintype "bidirectional"))
      (node (ref "U7") (pin "28") (pinfunction "PC5(ADC5/SCL)_28") (pintype "bidirectional"))
      (node (ref "U8") (pin "5") (pinfunction "SCL_5") (pintype "input"))
    )
    (net (code "58") (name "SDA") (class "Default")
      (node (ref "R19") (pin "1") (pinfunction "1_1") (pintype "passive"))
      (node (ref "SH11") (pin "A4") (pinfunction "A4_A4") (pintype "bidirectional"))
      (node (ref "U7") (pin "27") (pinfunction "PC4(ADC4/SDA)_27") (pintype "bidirectional"))
      (node (ref "U8") (pin "6") (pinfunction "SDA_6") (pintype "bidirectional"))
    )
    (net (code "59") (name "TXD") (class "Default")
      (node (ref "SH11") (pin "TX") (pinfunction "TX_TX") (pintype "bidirectional"))
      (node (ref "SV1") (pin "2") (pinfunction "2_2") (pintype "passive"))
      (node (ref "U7") (pin "31") (pinfunction "PD1(TXD)_31") (pintype "bidirectional"))
    )
    (net (code "60") (name "V+") (class "Default")
      (node (ref "C11") (pin "1") (pinfunction "1_1") (pintype "passive"))
      (node (ref "D2") (pin "C") (pinfunction "C_C") (pintype "passive"))
      (node (ref "L5") (pin "1") (pinfunction "1_1") (pintype "passive"))
      (node (ref "R16") (pin "2") (pinfunction "2_2") (pintype "passive"))
      (node (ref "SH11") (pin "VIN") (pinfunction "VIN_VIN") (pintype "bidirectional"))
      (node (ref "U4") (pin "3") (pinfunction "IN_3") (pintype "input"))
    )
    (net (code "61") (name "unconnected-(ANT1-PadNC)") (class "Default")
      (node (ref "ANT1") (pin "NC") (pinfunction "NC_NC") (pintype "bidirectional"))
    )
    (net (code "62") (name "unconnected-(SH11-*D3-PadD3)") (class "Default")
      (node (ref "SH11") (pin "D3") (pinfunction "*D3_D3") (pintype "bidirectional"))
    )
    (net (code "63") (name "unconnected-(SH11-PadAREF)") (class "Default")
      (node (ref "SH11") (pin "AREF") (pinfunction "AREF_AREF") (pintype "bidirectional"))
    )
    (net (code "64") (name "unconnected-(SH11-PadD2)") (class "Default")
      (node (ref "SH11") (pin "D2") (pinfunction "D2_D2") (pintype "bidirectional"))
    )
    (net (code "65") (name "unconnected-(SH11-PadIOREF)") (class "Default")
      (node (ref "SH11") (pin "IOREF") (pinfunction "IOREF_IOREF") (pintype "bidirectional"))
    )
    (net (code "66") (name "unconnected-(SH11-PadRES)") (class "Default")
      (node (ref "SH11") (pin "RES") (pinfunction "RES_RES") (pintype "bidirectional"))
    )
    (net (code "67") (name "unconnected-(U3-Pad4_TIMEPULSE)") (class "Default")
      (node (ref "U3") (pin "4_TIMEPULSE") (pinfunction "4_TIMEPULSE_4_TIMEPULSE") (pintype "bidirectional"))
    )
    (net (code "68") (name "unconnected-(U3-Pad5_EXTINT0)") (class "Default")
      (node (ref "U3") (pin "5_EXTINT0") (pinfunction "5_EXTINT0_5_EXTINT0") (pintype "bidirectional"))
    )
    (net (code "69") (name "unconnected-(U3-Pad13_ANTON)") (class "Default")
      (node (ref "U3") (pin "13_ANTON") (pinfunction "13_ANTON_13_ANTON") (pintype "bidirectional"))
    )
    (net (code "70") (name "unconnected-(U3-Pad14_VCC_RF)") (class "Default")
      (node (ref "U3") (pin "14_VCC_RF") (pinfunction "14_VCC_RF_14_VCC_RF") (pintype "bidirectional"))
    )
    (net (code "71") (name "unconnected-(U3-Pad15_RESERVED)") (class "Default")
      (node (ref "U3") (pin "15_RESERVED") (pinfunction "15_RESERVED_15_RESERVED") (pintype "bidirectional"))
    )
    (net (code "72") (name "unconnected-(U3-Pad16_SDA2)") (class "Default")
      (node (ref "U3") (pin "16_SDA2") (pinfunction "16_SDA2_16_SDA2") (pintype "bidirectional"))
    )
    (net (code "73") (name "unconnected-(U3-Pad17_SCL2)") (class "Default")
      (node (ref "U3") (pin "17_SCL2") (pinfunction "17_SCL2_17_SCL2") (pintype "bidirectional"))
    )
    (net (code "74") (name "unconnected-(U3-Pad18_RESERVED)") (class "Default")
      (node (ref "U3") (pin "18_RESERVED") (pinfunction "18_RESERVED_18_RESERVED") (pintype "bidirectional"))
    )
    (net (code "75") (name "unconnected-(U7-ADC6-Pad19)") (class "Default")
      (node (ref "U7") (pin "19") (pinfunction "ADC6_19") (pintype "bidirectional"))
    )
    (net (code "76") (name "unconnected-(U7-ADC7-Pad22)") (class "Default")
      (node (ref "U7") (pin "22") (pinfunction "ADC7_22") (pintype "bidirectional"))
    )
    (net (code "77") (name "unconnected-(U7-PB1(OC1A)-Pad13)") (class "Default")
      (node (ref "U7") (pin "13") (pinfunction "PB1(OC1A)_13") (pintype "bidirectional"))
    )
    (net (code "78") (name "unconnected-(U9D-OUT-Pad14)") (class "Default")
      (node (ref "U9") (pin "14") (pinfunction "OUT_14") (pintype "output"))
    )
  )
)
